# HW2.net
KiCad netlist of a schematic drawn in EAGLE
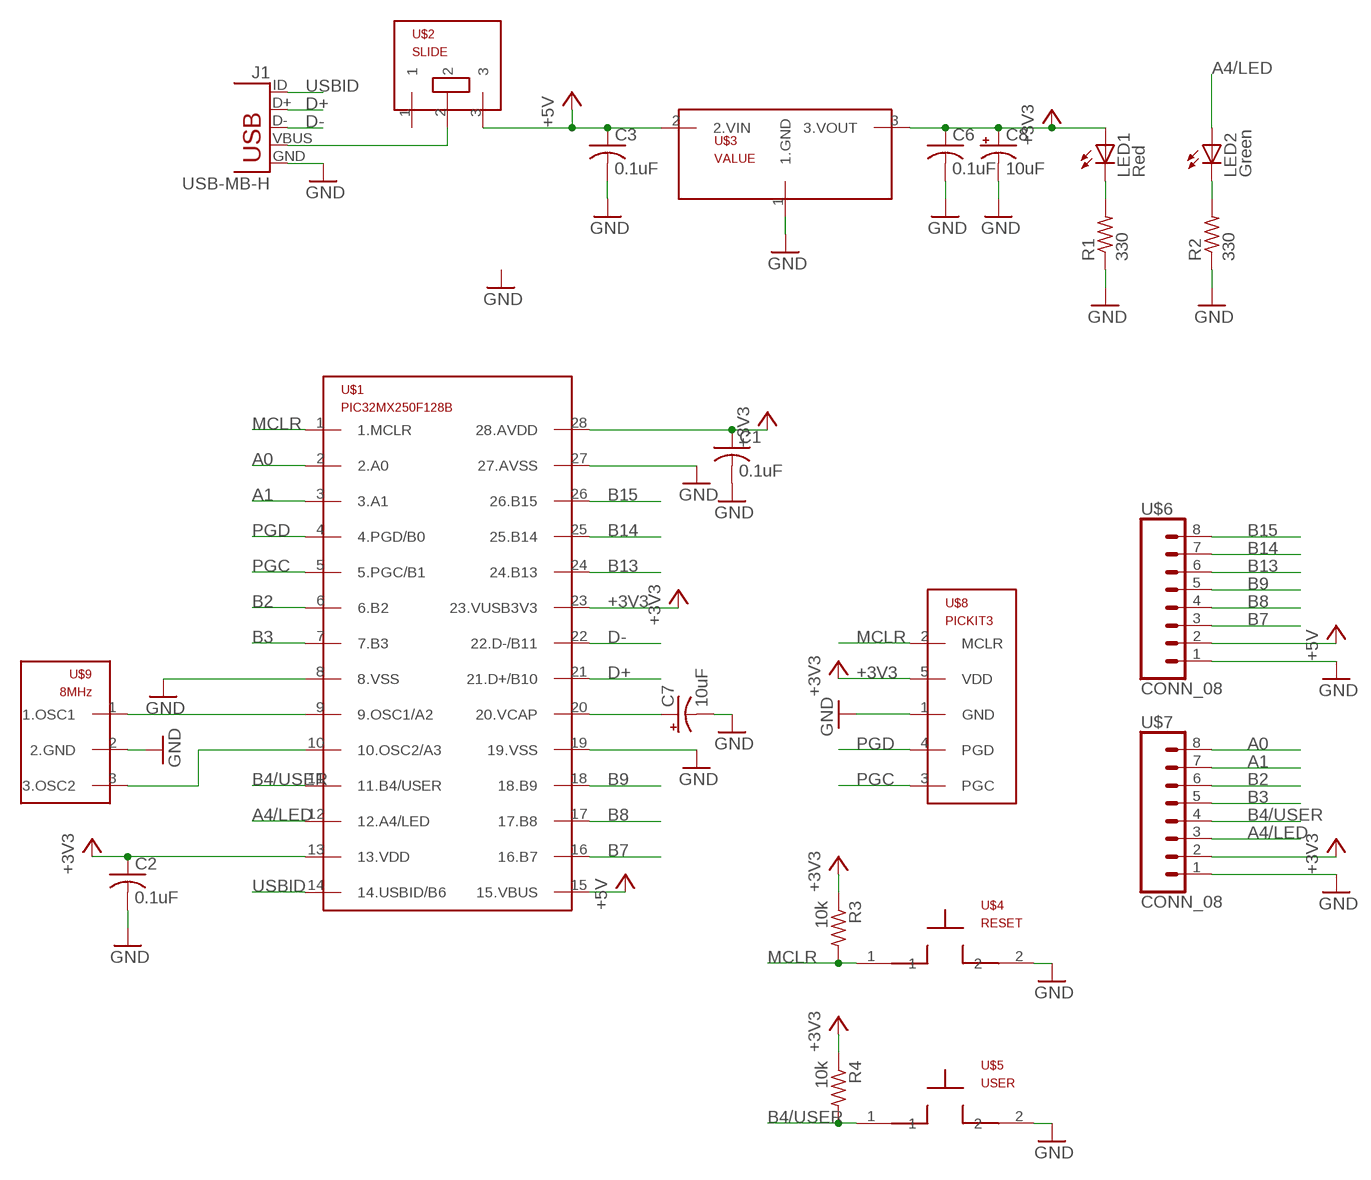
[diagram p0: schematic, sheet 1]

(export (version "E")
  (design (tool "Eeschema 10.0.6"))
  (components
    (comp (ref "C1")
      (value "0.1uF")
      (footprint "eagle-import:C025-025X050")
      (libsource (lib "eagle-import") (part "C-US025-025X050"))
    )
    (comp (ref "C2")
      (value "0.1uF")
      (footprint "eagle-import:C025-025X050")
      (libsource (lib "eagle-import") (part "C-US025-025X050"))
    )
    (comp (ref "C3")
      (value "0.1uF")
      (footprint "eagle-import:C025-025X050")
      (libsource (lib "eagle-import") (part "C-US025-025X050"))
    )
    (comp (ref "C6")
      (value "0.1uF")
      (footprint "eagle-import:C025-025X050")
      (libsource (lib "eagle-import") (part "C-US025-025X050"))
    )
    (comp (ref "C7")
      (value "10uF")
      (footprint "eagle-import:B45181B")
      (libsource (lib "eagle-import") (part "CPOL-USB45181B"))
    )
    (comp (ref "C8")
      (value "10uF")
      (footprint "eagle-import:B45181B")
      (libsource (lib "eagle-import") (part "CPOL-USB45181B"))
    )
    (comp (ref "J1")
      (value "USB-MB-H")
      (footprint "eagle-import:USB-MB-H")
      (libsource (lib "eagle-import") (part "USB-MB-H"))
    )
    (comp (ref "LED1")
      (value "Red")
      (footprint "eagle-import:LED3MM")
      (libsource (lib "eagle-import") (part "LED3MM"))
    )
    (comp (ref "LED2")
      (value "Green")
      (footprint "eagle-import:LED3MM")
      (libsource (lib "eagle-import") (part "LED3MM"))
    )
    (comp (ref "R1")
      (value "330")
      (footprint "eagle-import:0207_10")
      (libsource (lib "eagle-import") (part "R-US_0207/10"))
    )
    (comp (ref "R2")
      (value "330")
      (footprint "eagle-import:0207_10")
      (libsource (lib "eagle-import") (part "R-US_0207/10"))
    )
    (comp (ref "R3")
      (value "10k")
      (footprint "eagle-import:0207_10")
      (libsource (lib "eagle-import") (part "R-US_0207/10"))
    )
    (comp (ref "R4")
      (value "10k")
      (footprint "eagle-import:0207_10")
      (libsource (lib "eagle-import") (part "R-US_0207/10"))
    )
    (comp (ref "U$1")
      (value "PIC32MX250F128B")
      (footprint "eagle-import:DIL28-3")
      (libsource (lib "eagle-import") (part "PIC32MX250F128B"))
    )
    (comp (ref "U$2")
      (value "SLIDE")
      (footprint "eagle-import:SLIDE")
      (libsource (lib "eagle-import") (part "SLIDE"))
    )
    (comp (ref "U$3")
      (value "MCP1702")
      (footprint "eagle-import:TO92")
      (libsource (lib "eagle-import") (part "MCP1702"))
    )
    (comp (ref "U$4")
      (value "RESET")
      (footprint "eagle-import:PB")
      (libsource (lib "eagle-import") (part "PB"))
    )
    (comp (ref "U$5")
      (value "USER")
      (footprint "eagle-import:PB")
      (libsource (lib "eagle-import") (part "PB"))
    )
    (comp (ref "U$6")
      (value "CONN_08")
      (footprint "eagle-import:1X08")
      (libsource (lib "eagle-import") (part "CONN_08"))
    )
    (comp (ref "U$7")
      (value "CONN_08")
      (footprint "eagle-import:1X08")
      (libsource (lib "eagle-import") (part "CONN_08"))
    )
    (comp (ref "U$8")
      (value "PICKIT3")
      (footprint "eagle-import:1X05")
      (libsource (lib "eagle-import") (part "PICKIT3"))
    )
    (comp (ref "U$9")
      (value "8MHz")
      (footprint "eagle-import:OSC")
      (libsource (lib "eagle-import") (part "OSC"))
    )
  )
  (nets
    (net (code "1") (name "+3V3") (class "Default")
      (node (ref "C1") (pin "1") (pinfunction "1_1") (pintype "passive"))
      (node (ref "C2") (pin "1") (pinfunction "1_1") (pintype "passive"))
      (node (ref "C6") (pin "1") (pinfunction "1_1") (pintype "passive"))
      (node (ref "C8") (pin "+") (pinfunction "+_+") (pintype "passive"))
      (node (ref "LED1") (pin "A") (pinfunction "A_A") (pintype "passive"))
      (node (ref "R3") (pin "1") (pinfunction "1_1") (pintype "passive"))
      (node (ref "R4") (pin "1") (pinfunction "1_1") (pintype "passive"))
      (node (ref "U$1") (pin "13") (pinfunction "13.VDD_13") (pintype "bidirectional"))
      (node (ref "U$1") (pin "23") (pinfunction "23.VUSB3V3_23") (pintype "bidirectional"))
      (node (ref "U$1") (pin "28") (pinfunction "28.AVDD_28") (pintype "bidirectional"))
      (node (ref "U$3") (pin "3") (pinfunction "3.VOUT_3") (pintype "bidirectional"))
      (node (ref "U$7") (pin "2") (pinfunction "2_2") (pintype "passive"))
      (node (ref "U$8") (pin "5") (pinfunction "VDD_5") (pintype "bidirectional"))
    )
    (net (code "2") (name "+5V") (class "Default")
      (node (ref "C3") (pin "1") (pinfunction "1_1") (pintype "passive"))
      (node (ref "U$1") (pin "15") (pinfunction "15.VBUS_15") (pintype "bidirectional"))
      (node (ref "U$2") (pin "3") (pinfunction "3_3") (pintype "bidirectional"))
      (node (ref "U$3") (pin "2") (pinfunction "2.VIN_2") (pintype "bidirectional"))
      (node (ref "U$6") (pin "2") (pinfunction "2_2") (pintype "passive"))
    )
    (net (code "3") (name "/A0") (class "Default")
      (node (ref "U$1") (pin "2") (pinfunction "2.A0_2") (pintype "bidirectional"))
      (node (ref "U$7") (pin "8") (pinfunction "8_8") (pintype "passive"))
    )
    (net (code "4") (name "/A1") (class "Default")
      (node (ref "U$1") (pin "3") (pinfunction "3.A1_3") (pintype "bidirectional"))
      (node (ref "U$7") (pin "7") (pinfunction "7_7") (pintype "passive"))
    )
    (net (code "5") (name "/A4{slash}LED") (class "Default")
      (node (ref "LED2") (pin "A") (pinfunction "A_A") (pintype "passive"))
      (node (ref "U$1") (pin "12") (pinfunction "12.A4/LED_12") (pintype "bidirectional"))
      (node (ref "U$7") (pin "3") (pinfunction "3_3") (pintype "passive"))
    )
    (net (code "6") (name "/B2") (class "Default")
      (node (ref "U$1") (pin "6") (pinfunction "6.B2_6") (pintype "bidirectional"))
      (node (ref "U$7") (pin "6") (pinfunction "6_6") (pintype "passive"))
    )
    (net (code "7") (name "/B3") (class "Default")
      (node (ref "U$1") (pin "7") (pinfunction "7.B3_7") (pintype "bidirectional"))
      (node (ref "U$7") (pin "5") (pinfunction "5_5") (pintype "passive"))
    )
    (net (code "8") (name "/B4{slash}USER") (class "Default")
      (node (ref "R4") (pin "2") (pinfunction "2_2") (pintype "passive"))
      (node (ref "U$1") (pin "11") (pinfunction "11.B4/USER_11") (pintype "bidirectional"))
      (node (ref "U$5") (pin "1") (pinfunction "1_1") (pintype "bidirectional"))
      (node (ref "U$7") (pin "4") (pinfunction "4_4") (pintype "passive"))
    )
    (net (code "9") (name "/B7") (class "Default")
      (node (ref "U$1") (pin "16") (pinfunction "16.B7_16") (pintype "bidirectional"))
      (node (ref "U$6") (pin "3") (pinfunction "3_3") (pintype "passive"))
    )
    (net (code "10") (name "/B8") (class "Default")
      (node (ref "U$1") (pin "17") (pinfunction "17.B8_17") (pintype "bidirectional"))
      (node (ref "U$6") (pin "4") (pinfunction "4_4") (pintype "passive"))
    )
    (net (code "11") (name "/B9") (class "Default")
      (node (ref "U$1") (pin "18") (pinfunction "18.B9_18") (pintype "bidirectional"))
      (node (ref "U$6") (pin "5") (pinfunction "5_5") (pintype "passive"))
    )
    (net (code "12") (name "/B13") (class "Default")
      (node (ref "U$1") (pin "24") (pinfunction "24.B13_24") (pintype "bidirectional"))
      (node (ref "U$6") (pin "6") (pinfunction "6_6") (pintype "passive"))
    )
    (net (code "13") (name "/B14") (class "Default")
      (node (ref "U$1") (pin "25") (pinfunction "25.B14_25") (pintype "bidirectional"))
      (node (ref "U$6") (pin "7") (pinfunction "7_7") (pintype "passive"))
    )
    (net (code "14") (name "/B15") (class "Default")
      (node (ref "U$1") (pin "26") (pinfunction "26.B15_26") (pintype "bidirectional"))
      (node (ref "U$6") (pin "8") (pinfunction "8_8") (pintype "passive"))
    )
    (net (code "15") (name "/D+") (class "Default")
      (node (ref "J1") (pin "D+") (pinfunction "D+_D+") (pintype "bidirectional"))
      (node (ref "U$1") (pin "21") (pinfunction "21.D+/B10_21") (pintype "bidirectional"))
    )
    (net (code "16") (name "/D-") (class "Default")
      (node (ref "J1") (pin "D-") (pinfunction "D-_D-") (pintype "bidirectional"))
      (node (ref "U$1") (pin "22") (pinfunction "22.D-/B11_22") (pintype "bidirectional"))
    )
    (net (code "17") (name "/MCLR") (class "Default")
      (node (ref "R3") (pin "2") (pinfunction "2_2") (pintype "passive"))
      (node (ref "U$1") (pin "1") (pinfunction "1.MCLR_1") (pintype "bidirectional"))
      (node (ref "U$4") (pin "1") (pinfunction "1_1") (pintype "bidirectional"))
      (node (ref "U$8") (pin "2") (pinfunction "MCLR_2") (pintype "bidirectional"))
    )
    (net (code "18") (name "/PGC") (class "Default")
      (node (ref "U$1") (pin "5") (pinfunction "5.PGC/B1_5") (pintype "bidirectional"))
      (node (ref "U$8") (pin "3") (pinfunction "PGC_3") (pintype "bidirectional"))
    )
    (net (code "19") (name "/PGD") (class "Default")
      (node (ref "U$1") (pin "4") (pinfunction "4.PGD/B0_4") (pintype "bidirectional"))
      (node (ref "U$8") (pin "4") (pinfunction "PGD_4") (pintype "bidirectional"))
    )
    (net (code "20") (name "/USBID") (class "Default")
      (node (ref "J1") (pin "ID") (pinfunction "D+1_ID") (pintype "bidirectional"))
      (node (ref "U$1") (pin "14") (pinfunction "14.USBID/B6_14") (pintype "bidirectional"))
    )
    (net (code "21") (name "GND") (class "Default")
      (node (ref "C1") (pin "2") (pinfunction "2_2") (pintype "passive"))
      (node (ref "C2") (pin "2") (pinfunction "2_2") (pintype "passive"))
      (node (ref "C3") (pin "2") (pinfunction "2_2") (pintype "passive"))
      (node (ref "C6") (pin "2") (pinfunction "2_2") (pintype "passive"))
      (node (ref "C7") (pin "-") (pinfunction "-_-") (pintype "passive"))
      (node (ref "C8") (pin "-") (pinfunction "-_-") (pintype "passive"))
      (node (ref "J1") (pin "GND") (pinfunction "GND_GND") (pintype "bidirectional"))
      (node (ref "R1") (pin "1") (pinfunction "1_1") (pintype "passive"))
      (node (ref "R2") (pin "1") (pinfunction "1_1") (pintype "passive"))
      (node (ref "U$1") (pin "19") (pinfunction "19.VSS_19") (pintype "bidirectional"))
      (node (ref "U$1") (pin "27") (pinfunction "27.AVSS_27") (pintype "bidirectional"))
      (node (ref "U$1") (pin "8") (pinfunction "8.VSS_8") (pintype "bidirectional"))
      (node (ref "U$3") (pin "1") (pinfunction "1.GND_1") (pintype "bidirectional"))
      (node (ref "U$4") (pin "2") (pinfunction "2_2") (pintype "bidirectional"))
      (node (ref "U$5") (pin "2") (pinfunction "2_2") (pintype "bidirectional"))
      (node (ref "U$6") (pin "1") (pinfunction "1_1") (pintype "passive"))
      (node (ref "U$7") (pin "1") (pinfunction "1_1") (pintype "passive"))
      (node (ref "U$8") (pin "1") (pinfunction "GND_1") (pintype "bidirectional"))
      (node (ref "U$9") (pin "2") (pinfunction "2.GND_2") (pintype "bidirectional"))
    )
    (net (code "22") (name "Net-(J1-PadVBUS)") (class "Default")
      (node (ref "J1") (pin "VBUS") (pinfunction "VBUS_VBUS") (pintype "bidirectional"))
      (node (ref "U$2") (pin "2") (pinfunction "2_2") (pintype "bidirectional"))
    )
    (net (code "23") (name "Net-(LED1-C)") (class "Default")
      (node (ref "LED1") (pin "K") (pinfunction "C_K") (pintype "passive"))
      (node (ref "R1") (pin "2") (pinfunction "2_2") (pintype "passive"))
    )
    (net (code "24") (name "Net-(LED2-C)") (class "Default")
      (node (ref "LED2") (pin "K") (pinfunction "C_K") (pintype "passive"))
      (node (ref "R2") (pin "2") (pinfunction "2_2") (pintype "passive"))
    )
    (net (code "25") (name "Net-(U$1-9.OSC1{slash}A2)") (class "Default")
      (node (ref "U$1") (pin "9") (pinfunction "9.OSC1/A2_9") (pintype "bidirectional"))
      (node (ref "U$9") (pin "1") (pinfunction "1.OSC1_1") (pintype "bidirectional"))
    )
    (net (code "26") (name "Net-(U$1-10.OSC2{slash}A3)") (class "Default")
      (node (ref "U$1") (pin "10") (pinfunction "10.OSC2/A3_10") (pintype "bidirectional"))
      (node (ref "U$9") (pin "3") (pinfunction "3.OSC2_3") (pintype "bidirectional"))
    )
    (net (code "27") (name "Net-(U$1-20.VCAP)") (class "Default")
      (node (ref "C7") (pin "+") (pinfunction "+_+") (pintype "passive"))
      (node (ref "U$1") (pin "20") (pinfunction "20.VCAP_20") (pintype "bidirectional"))
    )
    (net (code "28") (name "unconnected-(U$2-Pad1)") (class "Default")
      (node (ref "U$2") (pin "1") (pinfunction "1_1") (pintype "bidirectional"))
    )
  )
)
